# isolator_si8662.net
KiCad netlist of a schematic drawn in Altium Designer
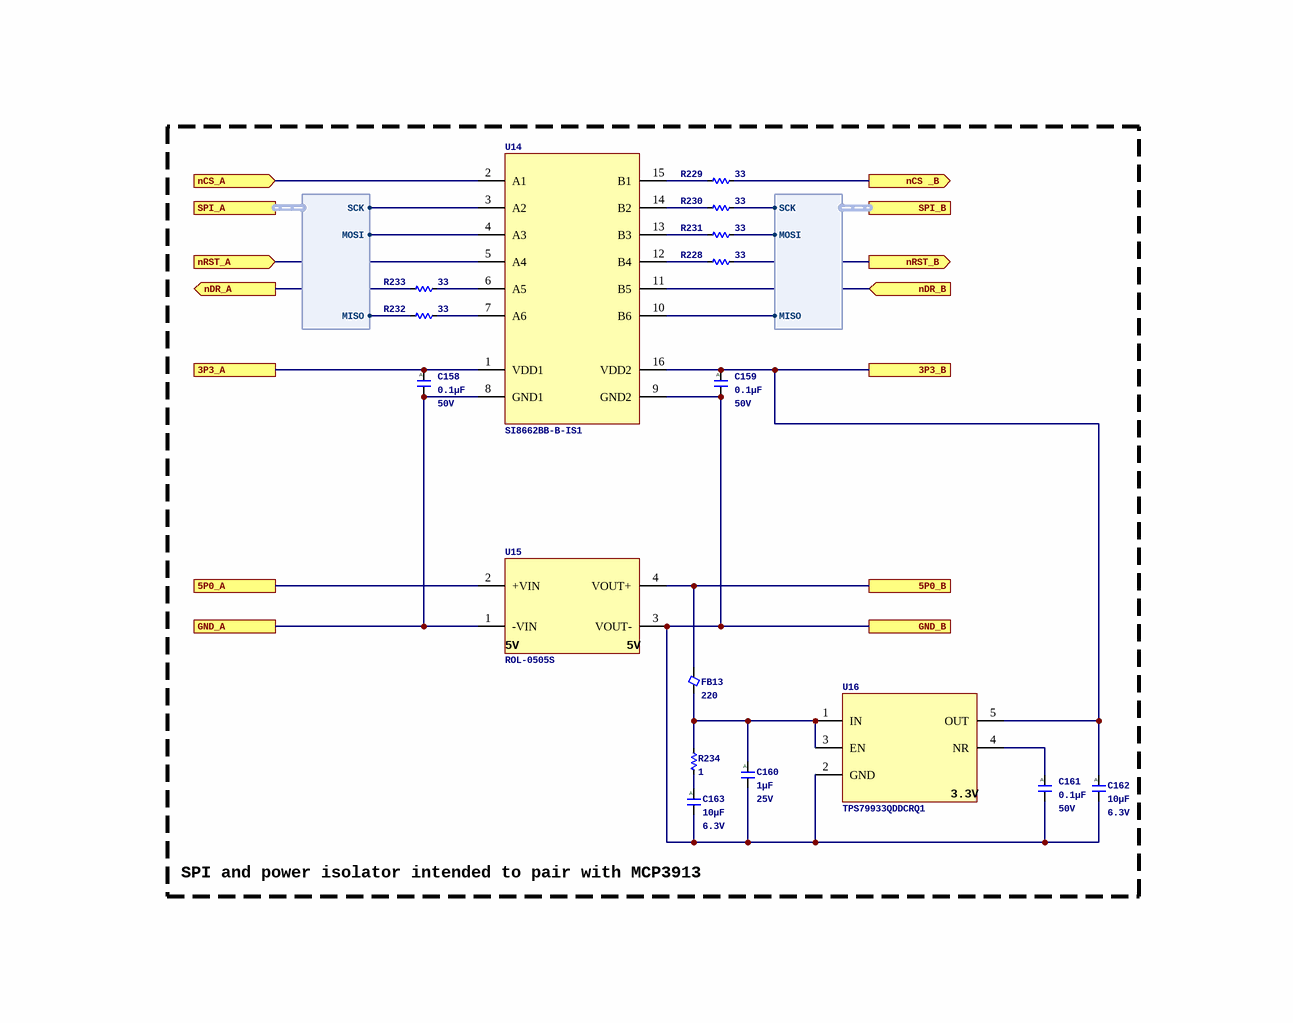
[diagram p0: isolator_si8662.SchDoc]

(export (version "E")
  (design (tool "Eeschema 10.0.6"))
  (components
    (comp (ref "C158")
      (value "CGA2B3X7R1H104M050BB")
      (footprint "C0402_0.55MM")
      (description "CAP CER 0.1UF 50V X7R 0402")
      (fields
        (field (name "CAPACITANCE") "0.1µF")
        (field (name "VOLTAGE - RATED") "50V")
        (field (name "TOLERANCE") "±20%")
        (field (name "MANUFACTURER") "TDK Corporation")
      )
      (libsource (lib "sscp") (part "__template_cap_auto"))
    )
    (comp (ref "C159")
      (value "CGA2B3X7R1H104M050BB")
      (footprint "C0402_0.55MM")
      (description "CAP CER 0.1UF 50V X7R 0402")
      (fields
        (field (name "CAPACITANCE") "0.1µF")
        (field (name "VOLTAGE - RATED") "50V")
        (field (name "TOLERANCE") "±20%")
        (field (name "MANUFACTURER") "TDK Corporation")
      )
      (libsource (lib "sscp") (part "__template_cap_auto"))
    )
    (comp (ref "C160")
      (value "CGJ3E1X7R1E105K080AC")
      (footprint "C0603_0.80MM")
      (description "CAP CER 1UF 25V X7R 0603")
      (fields
        (field (name "CAPACITANCE") "1µF")
        (field (name "VOLTAGE - RATED") "25V")
        (field (name "TOLERANCE") "±10%")
        (field (name "MANUFACTURER") "TDK Corporation")
      )
      (libsource (lib "sscp") (part "__template_cap_auto"))
    )
    (comp (ref "C161")
      (value "CGA2B3X7R1H104M050BB")
      (footprint "C0402_0.55MM")
      (description "CAP CER 0.1UF 50V X7R 0402")
      (fields
        (field (name "CAPACITANCE") "0.1µF")
        (field (name "VOLTAGE - RATED") "50V")
        (field (name "TOLERANCE") "±20%")
        (field (name "MANUFACTURER") "TDK Corporation")
      )
      (libsource (lib "sscp") (part "__template_cap_auto"))
    )
    (comp (ref "C162")
      (value "CGA4J1X7R0J106M125AC")
      (footprint "C0805_1.45MM")
      (description "CAP CER 10UF 6.3V X7R 0805")
      (fields
        (field (name "CAPACITANCE") "10µF")
        (field (name "VOLTAGE - RATED") "6.3V")
        (field (name "TOLERANCE") "±20%")
        (field (name "MANUFACTURER") "TDK Corporation")
      )
      (libsource (lib "sscp") (part "__template_cap_auto"))
    )
    (comp (ref "C163")
      (value "CGA4J1X7R0J106M125AC")
      (footprint "C0805_1.45MM")
      (description "CAP CER 10UF 6.3V X7R 0805")
      (fields
        (field (name "CAPACITANCE") "10µF")
        (field (name "VOLTAGE - RATED") "6.3V")
        (field (name "TOLERANCE") "±20%")
        (field (name "MANUFACTURER") "TDK Corporation")
      )
      (libsource (lib "sscp") (part "__template_cap_auto"))
    )
    (comp (ref "FB13")
      (value "MPZ1005S221ET000")
      (footprint "FB0402_0.55MM")
      (description "FERRITE BEAD 220 OHM 0402 1LN")
      (fields
        (field (name "IMPEDANCE (OHMS @ 100MHZ)") "220")
        (field (name "MANUFACTURER") "TDK Corporation")
      )
      (libsource (lib "sscp") (part "__template_ferrite"))
    )
    (comp (ref "R228")
      (value "ERJ-2RKF33R0X")
      (footprint "R0402_0.40MM")
      (description "RES SMD 33 OHM 1% 1/10W 0402")
      (fields
        (field (name "RESISTANCE") "33")
        (field (name "TOLERANCE") "±1%")
        (field (name "MANUFACTURER") "Panasonic Electronic Components")
      )
      (libsource (lib "sscp") (part "__template_resistor"))
    )
    (comp (ref "R229")
      (value "ERJ-2RKF33R0X")
      (footprint "R0402_0.40MM")
      (description "RES SMD 33 OHM 1% 1/10W 0402")
      (fields
        (field (name "RESISTANCE") "33")
        (field (name "TOLERANCE") "±1%")
        (field (name "MANUFACTURER") "Panasonic Electronic Components")
      )
      (libsource (lib "sscp") (part "__template_resistor"))
    )
    (comp (ref "R230")
      (value "ERJ-2RKF33R0X")
      (footprint "R0402_0.40MM")
      (description "RES SMD 33 OHM 1% 1/10W 0402")
      (fields
        (field (name "RESISTANCE") "33")
        (field (name "TOLERANCE") "±1%")
        (field (name "MANUFACTURER") "Panasonic Electronic Components")
      )
      (libsource (lib "sscp") (part "__template_resistor"))
    )
    (comp (ref "R231")
      (value "ERJ-2RKF33R0X")
      (footprint "R0402_0.40MM")
      (description "RES SMD 33 OHM 1% 1/10W 0402")
      (fields
        (field (name "RESISTANCE") "33")
        (field (name "TOLERANCE") "±1%")
        (field (name "MANUFACTURER") "Panasonic Electronic Components")
      )
      (libsource (lib "sscp") (part "__template_resistor"))
    )
    (comp (ref "R232")
      (value "ERJ-2RKF33R0X")
      (footprint "R0402_0.40MM")
      (description "RES SMD 33 OHM 1% 1/10W 0402")
      (fields
        (field (name "RESISTANCE") "33")
        (field (name "TOLERANCE") "±1%")
        (field (name "MANUFACTURER") "Panasonic Electronic Components")
      )
      (libsource (lib "sscp") (part "__template_resistor"))
    )
    (comp (ref "R233")
      (value "ERJ-2RKF33R0X")
      (footprint "R0402_0.40MM")
      (description "RES SMD 33 OHM 1% 1/10W 0402")
      (fields
        (field (name "RESISTANCE") "33")
        (field (name "TOLERANCE") "±1%")
        (field (name "MANUFACTURER") "Panasonic Electronic Components")
      )
      (libsource (lib "sscp") (part "__template_resistor"))
    )
    (comp (ref "R234")
      (value "ERJ-2BQF1R0X")
      (footprint "R0402_0.40MM")
      (description "RES SMD 1 OHM 1% 1/6W 0402")
      (fields
        (field (name "RESISTANCE") "1")
        (field (name "TOLERANCE") "±1%")
        (field (name "MANUFACTURER") "Panasonic Electronic Components")
      )
      (libsource (lib "sscp") (part "__template_resistor"))
    )
    (comp (ref "U14")
      (value "SI8662BB-B-IS1")
      (footprint "16SOIC150")
      (description "6-ch 2.5kV Isolator, 150M, 4/2, NB SOIC16, lead free")
      (fields (field (name "MANUFACTURER") "Skyworks Solutions"))
      (libsource (lib "SSCP") (part "ISO_SI8662BB-B-IS1"))
    )
    (comp (ref "U15")
      (value "ROL-0505S")
      (footprint "4SIP")
      (description "5V to 5V isolated power supply module")
      (fields (field (name "MANUFACTURER") "Recom"))
      (libsource (lib "SSCP") (part "CONV_DCDC_5V_0.5W_ROL-0505S"))
    )
    (comp (ref "U16")
      (value "TPS79933QDDCRQ1")
      (footprint "5SOT23")
      (description "Fixed Positive LDO Regulator, 3.3V, 0.16V Dropout, BICMOS, PDSO5")
      (fields (field (name "MANUFACTURER") "Texas Instruments"))
      (libsource (lib "SSCP") (part "LDO_TPS79933QDDCRQ1"))
    )
  )
  (nets
    (net (code "2") (name "/3P3_A") (class "Default")
      (node (ref "C158") (pin "1") (pintype "passive"))
      (node (ref "U14") (pin "1") (pinfunction "VDD1_1") (pintype "passive"))
    )
    (net (code "3") (name "/3P3_B") (class "Default")
      (node (ref "C159") (pin "1") (pintype "passive"))
      (node (ref "C162") (pin "1") (pintype "passive"))
      (node (ref "U14") (pin "16") (pinfunction "VDD2_16") (pintype "passive"))
      (node (ref "U16") (pin "5") (pinfunction "OUT_5") (pintype "passive"))
    )
    (net (code "4") (name "/5P0_A") (class "Default")
      (node (ref "U15") (pin "2") (pinfunction "+VIN_2") (pintype "passive"))
    )
    (net (code "5") (name "/5P0_B") (class "Default")
      (node (ref "FB13") (pin "2") (pintype "passive"))
      (node (ref "U15") (pin "4") (pinfunction "VOUT+_4") (pintype "passive"))
    )
    (net (code "6") (name "/GND_A") (class "Default")
      (node (ref "C158") (pin "2") (pintype "passive"))
      (node (ref "U14") (pin "8") (pinfunction "GND1_8") (pintype "passive"))
      (node (ref "U15") (pin "1") (pinfunction "-VIN_1") (pintype "passive"))
    )
    (net (code "7") (name "/GND_B") (class "Default")
      (node (ref "C159") (pin "2") (pintype "passive"))
      (node (ref "C160") (pin "2") (pintype "passive"))
      (node (ref "C161") (pin "2") (pintype "passive"))
      (node (ref "C162") (pin "2") (pintype "passive"))
      (node (ref "C163") (pin "2") (pintype "passive"))
      (node (ref "U14") (pin "9") (pinfunction "GND2_9") (pintype "passive"))
      (node (ref "U15") (pin "3") (pinfunction "VOUT-_3") (pintype "passive"))
      (node (ref "U16") (pin "2") (pinfunction "GND_2") (pintype "passive"))
    )
    (net (code "8") (name "/nCS _B") (class "Default") (node (ref "R229") (pin "1") (pintype "passive")))
    (net (code "9") (name "/nCS_A") (class "Default")
      (node (ref "U14") (pin "2") (pinfunction "A1_2") (pintype "passive"))
    )
    (net (code "10") (name "/nDR_A") (class "Default") (node (ref "R233") (pin "2") (pintype "passive")))
    (net (code "11") (name "/nDR_B") (class "Default")
      (node (ref "U14") (pin "11") (pinfunction "B5_11") (pintype "passive"))
    )
    (net (code "12") (name "/nRST_A") (class "Default")
      (node (ref "U14") (pin "5") (pinfunction "A4_5") (pintype "passive"))
    )
    (net (code "13") (name "/nRST_B") (class "Default") (node (ref "R228") (pin "1") (pintype "passive")))
    (net (code "15") (name "Net-(C163-Pad1)") (class "Default")
      (node (ref "C163") (pin "1") (pintype "passive"))
      (node (ref "R234") (pin "1") (pintype "passive"))
    )
    (net (code "16") (name "Net-(U14-A5)") (class "Default")
      (node (ref "R233") (pin "1") (pintype "passive"))
      (node (ref "U14") (pin "6") (pinfunction "A5_6") (pintype "passive"))
    )
    (net (code "17") (name "Net-(U14-A6)") (class "Default")
      (node (ref "R232") (pin "1") (pintype "passive"))
      (node (ref "U14") (pin "7") (pinfunction "A6_7") (pintype "passive"))
    )
    (net (code "18") (name "Net-(U14-B1)") (class "Default")
      (node (ref "R229") (pin "2") (pintype "passive"))
      (node (ref "U14") (pin "15") (pinfunction "B1_15") (pintype "passive"))
    )
    (net (code "19") (name "Net-(U14-B2)") (class "Default")
      (node (ref "R230") (pin "2") (pintype "passive"))
      (node (ref "U14") (pin "14") (pinfunction "B2_14") (pintype "passive"))
    )
    (net (code "20") (name "Net-(U14-B3)") (class "Default")
      (node (ref "R231") (pin "2") (pintype "passive"))
      (node (ref "U14") (pin "13") (pinfunction "B3_13") (pintype "passive"))
    )
    (net (code "21") (name "Net-(U14-B4)") (class "Default")
      (node (ref "R228") (pin "2") (pintype "passive"))
      (node (ref "U14") (pin "12") (pinfunction "B4_12") (pintype "passive"))
    )
    (net (code "22") (name "Net-(U16-EN)") (class "Default")
      (node (ref "C160") (pin "1") (pintype "passive"))
      (node (ref "FB13") (pin "1") (pintype "passive"))
      (node (ref "R234") (pin "2") (pintype "passive"))
      (node (ref "U16") (pin "1") (pinfunction "IN_1") (pintype "passive"))
      (node (ref "U16") (pin "3") (pinfunction "EN_3") (pintype "passive"))
    )
    (net (code "23") (name "Net-(U16-NR)") (class "Default")
      (node (ref "C161") (pin "1") (pintype "passive"))
      (node (ref "U16") (pin "4") (pinfunction "NR_4") (pintype "passive"))
    )
    (net (code "24") (name "unconnected-(R230-Pad1)") (class "Default")
      (node (ref "R230") (pin "1") (pintype "passive"))
    )
    (net (code "25") (name "unconnected-(R231-Pad1)") (class "Default")
      (node (ref "R231") (pin "1") (pintype "passive"))
    )
    (net (code "26") (name "unconnected-(R232-Pad2)") (class "Default")
      (node (ref "R232") (pin "2") (pintype "passive"))
    )
    (net (code "27") (name "unconnected-(U14-A2-Pad3)") (class "Default")
      (node (ref "U14") (pin "3") (pinfunction "A2_3") (pintype "passive"))
    )
    (net (code "28") (name "unconnected-(U14-A3-Pad4)") (class "Default")
      (node (ref "U14") (pin "4") (pinfunction "A3_4") (pintype "passive"))
    )
    (net (code "29") (name "unconnected-(U14-B6-Pad10)") (class "Default")
      (node (ref "U14") (pin "10") (pinfunction "B6_10") (pintype "passive"))
    )
  )
)
